# board.net
KiCad netlist of a schematic drawn in EAGLE
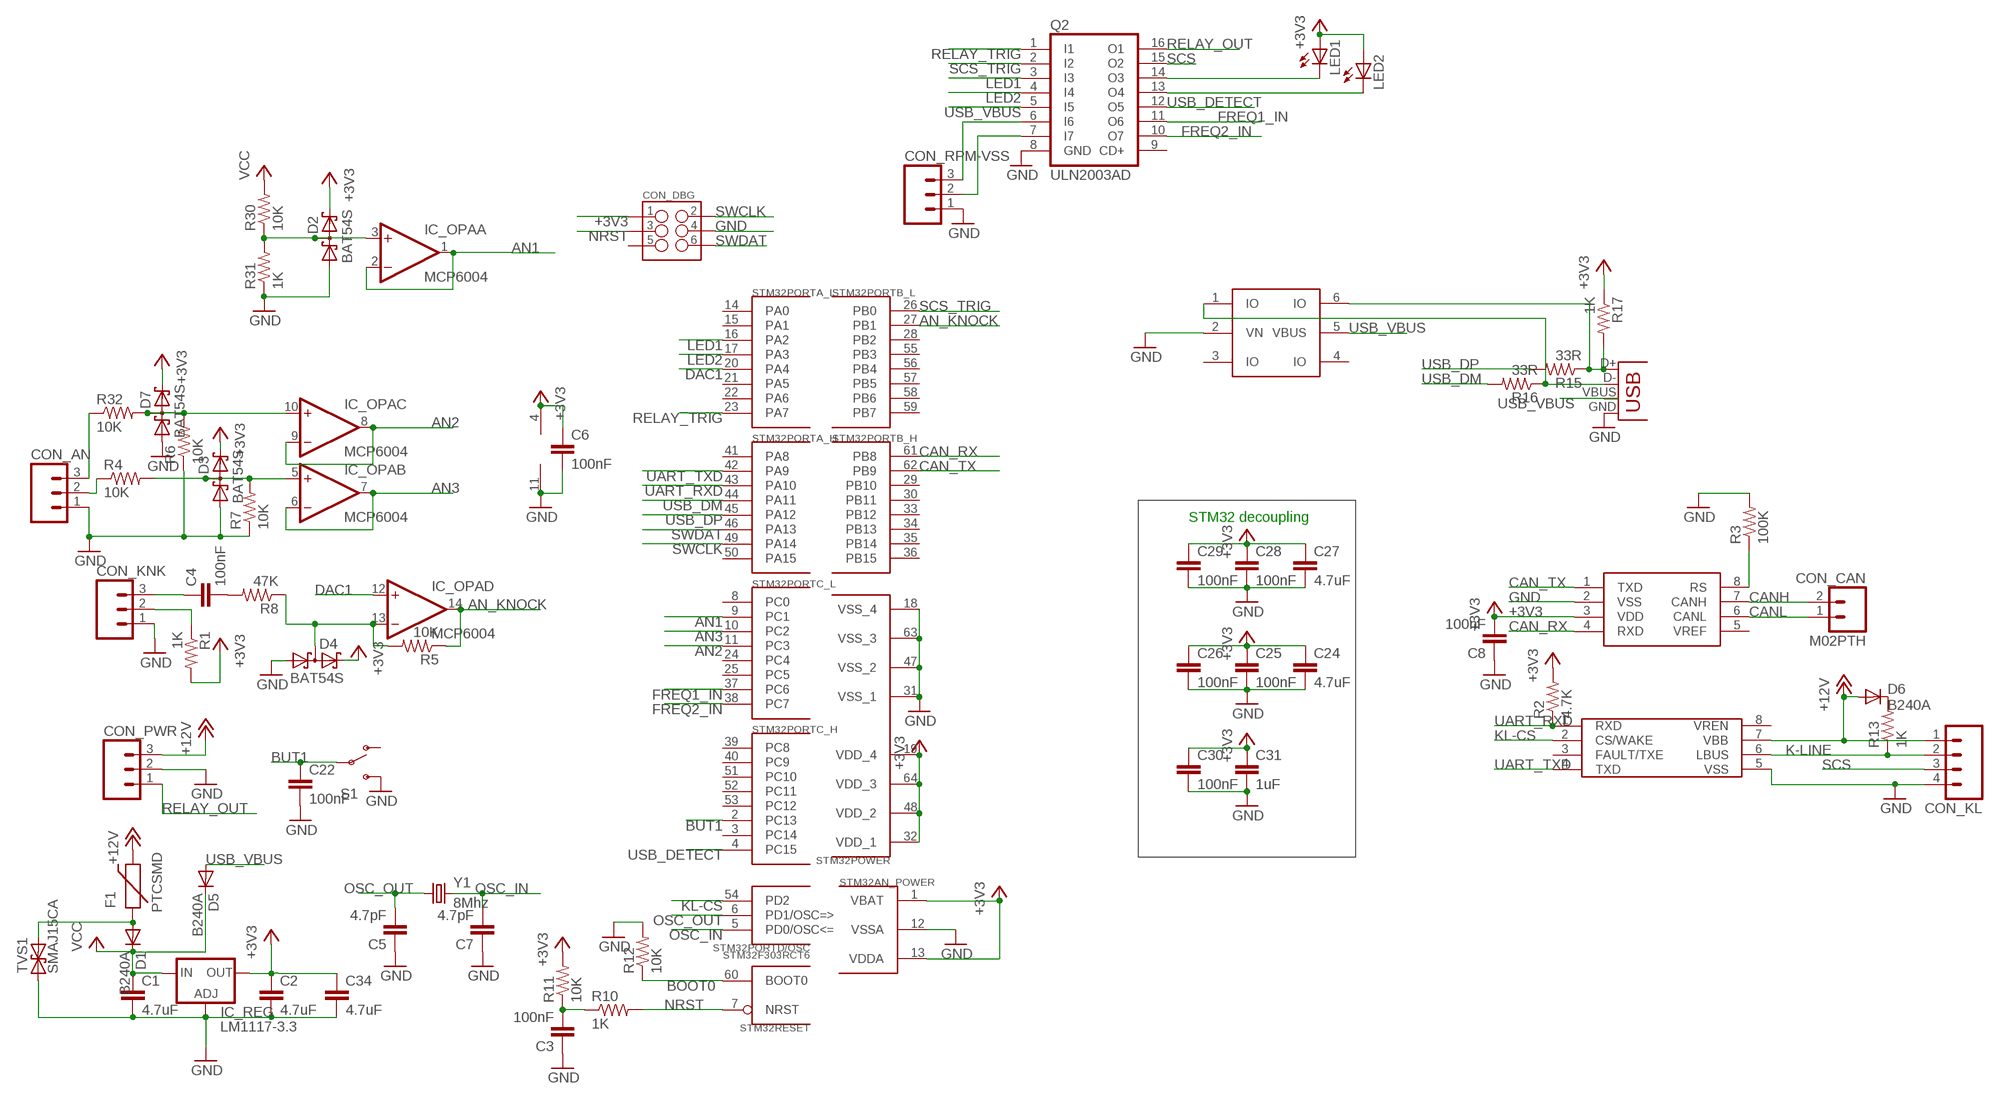
[diagram p0: schematic, sheet 1]

(export (version "E")
  (design (tool "Eeschema 10.0.6"))
  (components
    (comp (ref "C1")
      (value "4.7uF")
      (footprint "eagle-import:0603-CAP")
      (libsource (lib "eagle-import") (part "SparkFun-Passives_CAP0603-CAP"))
    )
    (comp (ref "C2")
      (value "4.7uF")
      (footprint "eagle-import:0603-CAP")
      (libsource (lib "eagle-import") (part "SparkFun-Passives_CAP0603-CAP"))
    )
    (comp (ref "C3")
      (value "100nF")
      (footprint "eagle-import:0603-CAP")
      (libsource (lib "eagle-import") (part "CAP0603-CAP"))
    )
    (comp (ref "C4")
      (value "100nF")
      (footprint "eagle-import:0603-CAP")
      (libsource (lib "eagle-import") (part "CAP0603-CAP"))
    )
    (comp (ref "C5")
      (value "4.7pF")
      (footprint "eagle-import:0603-CAP")
      (libsource (lib "eagle-import") (part "CAP0603-CAP"))
    )
    (comp (ref "C6")
      (value "100nF")
      (footprint "eagle-import:0603-CAP")
      (libsource (lib "eagle-import") (part "CAP0603-CAP"))
    )
    (comp (ref "C7")
      (value "4.7pF")
      (footprint "eagle-import:0603-CAP")
      (libsource (lib "eagle-import") (part "CAP0603-CAP"))
    )
    (comp (ref "C8")
      (value "100nF")
      (footprint "eagle-import:0603-CAP")
      (libsource (lib "eagle-import") (part "CAP0603-CAP"))
    )
    (comp (ref "C22")
      (value "100nF")
      (footprint "eagle-import:0603-CAP")
      (libsource (lib "eagle-import") (part "CAP0603-CAP"))
    )
    (comp (ref "C24")
      (value "4.7uF")
      (footprint "eagle-import:0603-CAP")
      (libsource (lib "eagle-import") (part "SparkFun-Passives_CAP0603-CAP"))
    )
    (comp (ref "C25")
      (value "100nF")
      (footprint "eagle-import:0603-CAP")
      (libsource (lib "eagle-import") (part "CAP0603-CAP"))
    )
    (comp (ref "C26")
      (value "100nF")
      (footprint "eagle-import:0603-CAP")
      (libsource (lib "eagle-import") (part "CAP0603-CAP"))
    )
    (comp (ref "C27")
      (value "4.7uF")
      (footprint "eagle-import:0603-CAP")
      (libsource (lib "eagle-import") (part "SparkFun-Passives_CAP0603-CAP"))
    )
    (comp (ref "C28")
      (value "100nF")
      (footprint "eagle-import:0603-CAP")
      (libsource (lib "eagle-import") (part "CAP0603-CAP"))
    )
    (comp (ref "C29")
      (value "100nF")
      (footprint "eagle-import:0603-CAP")
      (libsource (lib "eagle-import") (part "CAP0603-CAP"))
    )
    (comp (ref "C30")
      (value "100nF")
      (footprint "eagle-import:0603-CAP")
      (libsource (lib "eagle-import") (part "CAP0603-CAP"))
    )
    (comp (ref "C31")
      (value "1uF")
      (footprint "eagle-import:0603-CAP")
      (libsource (lib "eagle-import") (part "CAP0603-CAP"))
    )
    (comp (ref "C34")
      (value "4.7uF")
      (footprint "eagle-import:0603-CAP")
      (libsource (lib "eagle-import") (part "SparkFun-Passives_CAP0603-CAP"))
    )
    (comp (ref "CON_AN")
      (value "M03PTH")
      (footprint "eagle-import:1X03")
      (libsource (lib "eagle-import") (part "M03PTH"))
    )
    (comp (ref "CON_CAN")
      (value "M02PTH")
      (footprint "eagle-import:1X02")
      (libsource (lib "eagle-import") (part "M02PTH"))
    )
    (comp (ref "CON_DBG")
      (value "M03X22X3_SILK_SM")
      (footprint "eagle-import:2X3")
      (libsource (lib "eagle-import") (part "M03X22X3_SILK_SM"))
    )
    (comp (ref "CON_KL")
      (value "M04PTH")
      (footprint "eagle-import:1X04")
      (libsource (lib "eagle-import") (part "M04PTH"))
    )
    (comp (ref "CON_KNK")
      (value "M03PTH")
      (footprint "eagle-import:1X03")
      (libsource (lib "eagle-import") (part "M03PTH"))
    )
    (comp (ref "CON_PWR")
      (value "M03PTH")
      (footprint "eagle-import:1X03")
      (libsource (lib "eagle-import") (part "M03PTH"))
    )
    (comp (ref "CON_RPM-VSS")
      (value "M03PTH")
      (footprint "eagle-import:1X03")
      (libsource (lib "eagle-import") (part "M03PTH"))
    )
    (comp (ref "D1")
      (value "B240A")
      (footprint "eagle-import:SMA-DIODE")
      (libsource (lib "eagle-import") (part "DIODESMA"))
    )
    (comp (ref "D2")
      (value "BAT54S")
      (footprint "eagle-import:SOT23")
      (libsource (lib "eagle-import") (part "BAT54S"))
    )
    (comp (ref "D3")
      (value "BAT54S")
      (footprint "eagle-import:SOT23")
      (libsource (lib "eagle-import") (part "BAT54S"))
    )
    (comp (ref "D4")
      (value "BAT54S")
      (footprint "eagle-import:SOT23")
      (libsource (lib "eagle-import") (part "BAT54S"))
    )
    (comp (ref "D5")
      (value "B240A")
      (footprint "eagle-import:SMA-DIODE")
      (libsource (lib "eagle-import") (part "DIODESMA"))
    )
    (comp (ref "D6")
      (value "B240A")
      (footprint "eagle-import:SMA-DIODE")
      (libsource (lib "eagle-import") (part "DIODESMA"))
    )
    (comp (ref "D7")
      (value "BAT54S")
      (footprint "eagle-import:SOT23")
      (libsource (lib "eagle-import") (part "BAT54S"))
    )
    (comp (ref "F1")
      (value "PTCSMD")
      (footprint "eagle-import:PTC-1206")
      (libsource (lib "eagle-import") (part "PTCSMD"))
    )
    (comp (ref "IC_CAN")
      (value "MAX3051")
      (footprint "eagle-import:SO08")
      (libsource (lib "eagle-import") (part "MCP2551"))
    )
    (comp (ref "IC_KLINE")
      (value "MCP2004")
      (footprint "eagle-import:SO08")
      (libsource (lib "eagle-import") (part "MCP2004"))
    )
    (comp (ref "IC_OPA")
      (value "MCP6004")
      (footprint "eagle-import:TSSOP14")
      (libsource (lib "eagle-import") (part "LMV324?MZ"))
    )
    (comp (ref "IC_REG")
      (value "LM1117-3.3")
      (footprint "eagle-import:DPACK")
      (libsource (lib "eagle-import") (part "LD117A?DT33TR"))
    )
    (comp (ref "JP1")
      (value "USBSMD")
      (footprint "eagle-import:USB-MINIB")
      (libsource (lib "eagle-import") (part "USBSMD"))
    )
    (comp (ref "LED1")
      (value "LED3MM")
      (footprint "eagle-import:LED3MM")
      (libsource (lib "eagle-import") (part "LED3MM"))
    )
    (comp (ref "LED2")
      (value "LED3MM")
      (footprint "eagle-import:LED3MM")
      (libsource (lib "eagle-import") (part "LED3MM"))
    )
    (comp (ref "Q2")
      (value "ULN2003AD")
      (footprint "eagle-import:SO16")
      (libsource (lib "eagle-import") (part "ULN2003AD"))
    )
    (comp (ref "R1")
      (value "1K")
      (footprint "eagle-import:0603-RES")
      (libsource (lib "eagle-import") (part "RESISTOR0603-RES"))
    )
    (comp (ref "R2")
      (value "4.7K")
      (footprint "eagle-import:0603-RES")
      (libsource (lib "eagle-import") (part "RESISTOR0603-RES"))
    )
    (comp (ref "R3")
      (value "100K")
      (footprint "eagle-import:0603-RES")
      (libsource (lib "eagle-import") (part "RESISTOR0603-RES"))
    )
    (comp (ref "R4")
      (value "10K")
      (footprint "eagle-import:0603-RES")
      (libsource (lib "eagle-import") (part "RESISTOR0603-RES"))
    )
    (comp (ref "R5")
      (value "10K")
      (footprint "eagle-import:0603-RES")
      (libsource (lib "eagle-import") (part "RESISTOR0603-RES"))
    )
    (comp (ref "R6")
      (value "10K")
      (footprint "eagle-import:0603-RES")
      (libsource (lib "eagle-import") (part "RESISTOR0603-RES"))
    )
    (comp (ref "R7")
      (value "10K")
      (footprint "eagle-import:0603-RES")
      (libsource (lib "eagle-import") (part "RESISTOR0603-RES"))
    )
    (comp (ref "R8")
      (value "47K")
      (footprint "eagle-import:0603-RES")
      (libsource (lib "eagle-import") (part "RESISTOR0603-RES"))
    )
    (comp (ref "R10")
      (value "1K")
      (footprint "eagle-import:0603-RES")
      (libsource (lib "eagle-import") (part "RESISTOR0603-RES"))
    )
    (comp (ref "R11")
      (value "10K")
      (footprint "eagle-import:0603-RES")
      (libsource (lib "eagle-import") (part "RESISTOR0603-RES"))
    )
    (comp (ref "R12")
      (value "10K")
      (footprint "eagle-import:0603-RES")
      (libsource (lib "eagle-import") (part "RESISTOR0603-RES"))
    )
    (comp (ref "R13")
      (value "1K")
      (footprint "eagle-import:0603-RES")
      (libsource (lib "eagle-import") (part "RESISTOR0603-RES"))
    )
    (comp (ref "R15")
      (value "33R")
      (footprint "eagle-import:0603-RES")
      (libsource (lib "eagle-import") (part "RESISTOR0603-RES"))
    )
    (comp (ref "R16")
      (value "33R")
      (footprint "eagle-import:0603-RES")
      (libsource (lib "eagle-import") (part "RESISTOR0603-RES"))
    )
    (comp (ref "R17")
      (value "1K")
      (footprint "eagle-import:0603-RES")
      (libsource (lib "eagle-import") (part "RESISTOR0603-RES"))
    )
    (comp (ref "R30")
      (value "10K")
      (footprint "eagle-import:0603-RES")
      (libsource (lib "eagle-import") (part "RESISTOR0603-RES"))
    )
    (comp (ref "R31")
      (value "1K")
      (footprint "eagle-import:0603-RES")
      (libsource (lib "eagle-import") (part "RESISTOR0603-RES"))
    )
    (comp (ref "R32")
      (value "10K")
      (footprint "eagle-import:0603-RES")
      (libsource (lib "eagle-import") (part "RESISTOR0603-RES"))
    )
    (comp (ref "S1")
      (value "SWITCH-SPDTPTH")
      (footprint "eagle-import:SWITCH-SPDT")
      (libsource (lib "eagle-import") (part "SWITCH-SPDTPTH"))
    )
    (comp (ref "STM32")
      (value "STM32F303RCT6")
      (footprint "eagle-import:TQFP64")
      (libsource (lib "eagle-import") (part "STM32F10XRXT6"))
    )
    (comp (ref "TVS1")
      (value "SMAJ15CA")
      (footprint "eagle-import:SMA-DIODE")
      (libsource (lib "eagle-import") (part "TVS"))
    )
    (comp (ref "TVS2")
      (value "NUP4201MR6")
      (footprint "eagle-import:SOT23-6")
      (libsource (lib "eagle-import") (part "NUP4201MR6"))
    )
    (comp (ref "Y1")
      (value "8Mhz")
      (footprint "eagle-import:HC49US")
      (libsource (lib "eagle-import") (part "CRYSTALHC49US"))
    )
  )
  (nets
    (net (code "1") (name "+3V3") (class "Default")
      (node (ref "C2") (pin "1") (pinfunction "1_1") (pintype "passive"))
      (node (ref "C24") (pin "1") (pinfunction "1_1") (pintype "passive"))
      (node (ref "C25") (pin "1") (pinfunction "1_1") (pintype "passive"))
      (node (ref "C26") (pin "1") (pinfunction "1_1") (pintype "passive"))
      (node (ref "C27") (pin "1") (pinfunction "1_1") (pintype "passive"))
      (node (ref "C28") (pin "1") (pinfunction "1_1") (pintype "passive"))
      (node (ref "C29") (pin "1") (pinfunction "1_1") (pintype "passive"))
      (node (ref "C30") (pin "1") (pinfunction "1_1") (pintype "passive"))
      (node (ref "C31") (pin "1") (pinfunction "1_1") (pintype "passive"))
      (node (ref "C34") (pin "1") (pinfunction "1_1") (pintype "passive"))
      (node (ref "C6") (pin "1") (pinfunction "1_1") (pintype "passive"))
      (node (ref "C8") (pin "2") (pinfunction "2_2") (pintype "passive"))
      (node (ref "CON_DBG") (pin "1") (pinfunction "1_1") (pintype "bidirectional"))
      (node (ref "D2") (pin "2") (pinfunction "C2_2") (pintype "passive"))
      (node (ref "D3") (pin "2") (pinfunction "C2_2") (pintype "passive"))
      (node (ref "D4") (pin "2") (pinfunction "C2_2") (pintype "passive"))
      (node (ref "D7") (pin "2") (pinfunction "C2_2") (pintype "passive"))
      (node (ref "IC_CAN") (pin "3") (pinfunction "VDD_3") (pintype "bidirectional"))
      (node (ref "IC_OPA") (pin "4") (pinfunction "V+_4") (pintype "power_in"))
      (node (ref "IC_REG") (pin "4") (pinfunction "OUT_4") (pintype "passive"))
      (node (ref "LED1") (pin "A") (pinfunction "A_A") (pintype "passive"))
      (node (ref "LED2") (pin "A") (pinfunction "A_A") (pintype "passive"))
      (node (ref "R1") (pin "2") (pinfunction "2_2") (pintype "passive"))
      (node (ref "R11") (pin "2") (pinfunction "2_2") (pintype "passive"))
      (node (ref "R17") (pin "1") (pinfunction "1_1") (pintype "passive"))
      (node (ref "R2") (pin "2") (pinfunction "2_2") (pintype "passive"))
      (node (ref "STM32") (pin "1") (pinfunction "VBAT_1") (pintype "power_in"))
      (node (ref "STM32") (pin "13") (pinfunction "VDDA_13") (pintype "power_in"))
      (node (ref "STM32") (pin "19") (pinfunction "VDD_4_19") (pintype "power_in"))
      (node (ref "STM32") (pin "32") (pinfunction "VDD_1_32") (pintype "power_in"))
      (node (ref "STM32") (pin "48") (pinfunction "VDD_2_48") (pintype "power_in"))
      (node (ref "STM32") (pin "64") (pinfunction "VDD_3_64") (pintype "power_in"))
    )
    (net (code "2") (name "+12V") (class "Default")
      (node (ref "CON_KL") (pin "1") (pinfunction "1_1") (pintype "passive"))
      (node (ref "CON_PWR") (pin "3") (pinfunction "3_3") (pintype "passive"))
      (node (ref "D6") (pin "A") (pinfunction "A_A") (pintype "passive"))
      (node (ref "F1") (pin "2") (pinfunction "2_2") (pintype "bidirectional"))
      (node (ref "IC_KLINE") (pin "7") (pinfunction "VBB_7") (pintype "bidirectional"))
    )
    (net (code "3") (name "/AN1") (class "Default")
      (node (ref "IC_OPA") (pin "1") (pinfunction "OUT_1") (pintype "output"))
      (node (ref "IC_OPA") (pin "2") (pinfunction "-IN_2") (pintype "input"))
      (node (ref "STM32") (pin "9") (pinfunction "PC1_9") (pintype "bidirectional"))
    )
    (net (code "4") (name "/AN2") (class "Default")
      (node (ref "IC_OPA") (pin "8") (pinfunction "OUT_8") (pintype "output"))
      (node (ref "IC_OPA") (pin "9") (pinfunction "-IN_9") (pintype "input"))
      (node (ref "STM32") (pin "11") (pinfunction "PC3_11") (pintype "bidirectional"))
    )
    (net (code "5") (name "/AN3") (class "Default")
      (node (ref "IC_OPA") (pin "6") (pinfunction "-IN_6") (pintype "input"))
      (node (ref "IC_OPA") (pin "7") (pinfunction "OUT_7") (pintype "output"))
      (node (ref "STM32") (pin "10") (pinfunction "PC2_10") (pintype "bidirectional"))
    )
    (net (code "6") (name "/AN_KNOCK") (class "Default")
      (node (ref "IC_OPA") (pin "14") (pinfunction "OUT_14") (pintype "output"))
      (node (ref "R5") (pin "1") (pinfunction "1_1") (pintype "passive"))
      (node (ref "STM32") (pin "27") (pinfunction "PB1_27") (pintype "bidirectional"))
    )
    (net (code "7") (name "/BOOT0") (class "Default")
      (node (ref "R12") (pin "1") (pinfunction "1_1") (pintype "passive"))
      (node (ref "STM32") (pin "60") (pinfunction "BOOT0_60") (pintype "input"))
    )
    (net (code "8") (name "/BUT1") (class "Default")
      (node (ref "C22") (pin "1") (pinfunction "1_1") (pintype "passive"))
      (node (ref "S1") (pin "2") (pinfunction "P_2") (pintype "passive"))
      (node (ref "STM32") (pin "2") (pinfunction "PC13_2") (pintype "bidirectional"))
    )
    (net (code "9") (name "/CANH") (class "Default")
      (node (ref "CON_CAN") (pin "2") (pinfunction "2_2") (pintype "passive"))
      (node (ref "IC_CAN") (pin "7") (pinfunction "CANH_7") (pintype "bidirectional"))
    )
    (net (code "10") (name "/CANL") (class "Default")
      (node (ref "CON_CAN") (pin "1") (pinfunction "1_1") (pintype "passive"))
      (node (ref "IC_CAN") (pin "6") (pinfunction "CANL_6") (pintype "bidirectional"))
    )
    (net (code "11") (name "/CAN_RX") (class "Default")
      (node (ref "IC_CAN") (pin "4") (pinfunction "RXD_4") (pintype "bidirectional"))
      (node (ref "STM32") (pin "61") (pinfunction "PB8_61") (pintype "bidirectional"))
    )
    (net (code "12") (name "/CAN_TX") (class "Default")
      (node (ref "IC_CAN") (pin "1") (pinfunction "TXD_1") (pintype "bidirectional"))
      (node (ref "STM32") (pin "62") (pinfunction "PB9_62") (pintype "bidirectional"))
    )
    (net (code "13") (name "/DAC1") (class "Default")
      (node (ref "IC_OPA") (pin "12") (pinfunction "+IN_12") (pintype "input"))
      (node (ref "STM32") (pin "20") (pinfunction "PA4_20") (pintype "bidirectional"))
    )
    (net (code "14") (name "/FREQ1_IN") (class "Default")
      (node (ref "Q2") (pin "11") (pinfunction "O6_11") (pintype "open_collector"))
      (node (ref "STM32") (pin "37") (pinfunction "PC6_37") (pintype "bidirectional"))
    )
    (net (code "15") (name "/FREQ2_IN") (class "Default")
      (node (ref "Q2") (pin "10") (pinfunction "O7_10") (pintype "open_collector"))
      (node (ref "STM32") (pin "38") (pinfunction "PC7_38") (pintype "bidirectional"))
    )
    (net (code "16") (name "/K-LINE") (class "Default")
      (node (ref "CON_KL") (pin "2") (pinfunction "2_2") (pintype "passive"))
      (node (ref "IC_KLINE") (pin "6") (pinfunction "LBUS_6") (pintype "bidirectional"))
      (node (ref "R13") (pin "1") (pinfunction "1_1") (pintype "passive"))
    )
    (net (code "17") (name "/KL-CS") (class "Default")
      (node (ref "IC_KLINE") (pin "2") (pinfunction "CS/WAKE_2") (pintype "bidirectional"))
      (node (ref "STM32") (pin "54") (pinfunction "PD2_54") (pintype "bidirectional"))
    )
    (net (code "18") (name "/LED1") (class "Default")
      (node (ref "Q2") (pin "3") (pinfunction "I3_3") (pintype "input"))
      (node (ref "STM32") (pin "16") (pinfunction "PA2_16") (pintype "bidirectional"))
    )
    (net (code "19") (name "/LED2") (class "Default")
      (node (ref "Q2") (pin "4") (pinfunction "I4_4") (pintype "input"))
      (node (ref "STM32") (pin "17") (pinfunction "PA3_17") (pintype "bidirectional"))
    )
    (net (code "20") (name "/NRST") (class "Default")
      (node (ref "CON_DBG") (pin "3") (pinfunction "3_3") (pintype "bidirectional"))
      (node (ref "R10") (pin "2") (pinfunction "2_2") (pintype "passive"))
      (node (ref "STM32") (pin "7") (pinfunction "NRST_7") (pintype "input"))
    )
    (net (code "21") (name "/OSC_IN") (class "Default")
      (node (ref "C7") (pin "2") (pinfunction "2_2") (pintype "passive"))
      (node (ref "STM32") (pin "5") (pinfunction "PD0/OSC<=_5") (pintype "bidirectional"))
      (node (ref "Y1") (pin "2") (pinfunction "2_2") (pintype "passive"))
    )
    (net (code "22") (name "/OSC_OUT") (class "Default")
      (node (ref "C5") (pin "2") (pinfunction "2_2") (pintype "passive"))
      (node (ref "STM32") (pin "6") (pinfunction "PD1/OSC=>_6") (pintype "bidirectional"))
      (node (ref "Y1") (pin "1") (pinfunction "1_1") (pintype "passive"))
    )
    (net (code "23") (name "/RELAY_OUT") (class "Default")
      (node (ref "CON_PWR") (pin "1") (pinfunction "1_1") (pintype "passive"))
      (node (ref "Q2") (pin "16") (pinfunction "O1_16") (pintype "open_collector"))
    )
    (net (code "24") (name "/RELAY_TRIG") (class "Default")
      (node (ref "Q2") (pin "1") (pinfunction "I1_1") (pintype "input"))
      (node (ref "STM32") (pin "23") (pinfunction "PA7_23") (pintype "bidirectional"))
    )
    (net (code "25") (name "/SCS") (class "Default")
      (node (ref "CON_KL") (pin "3") (pinfunction "3_3") (pintype "passive"))
      (node (ref "Q2") (pin "15") (pinfunction "O2_15") (pintype "open_collector"))
    )
    (net (code "26") (name "/SCS_TRIG") (class "Default")
      (node (ref "Q2") (pin "2") (pinfunction "I2_2") (pintype "input"))
      (node (ref "STM32") (pin "26") (pinfunction "PB0_26") (pintype "bidirectional"))
    )
    (net (code "27") (name "/SWCLK") (class "Default")
      (node (ref "CON_DBG") (pin "2") (pinfunction "2_2") (pintype "bidirectional"))
      (node (ref "STM32") (pin "49") (pinfunction "PA14_49") (pintype "bidirectional"))
    )
    (net (code "28") (name "/SWDAT") (class "Default")
      (node (ref "CON_DBG") (pin "6") (pinfunction "6_6") (pintype "bidirectional"))
      (node (ref "STM32") (pin "46") (pinfunction "PA13_46") (pintype "bidirectional"))
    )
    (net (code "29") (name "/UART_RXD") (class "Default")
      (node (ref "IC_KLINE") (pin "1") (pinfunction "RXD_1") (pintype "bidirectional"))
      (node (ref "R2") (pin "1") (pinfunction "1_1") (pintype "passive"))
      (node (ref "STM32") (pin "43") (pinfunction "PA10_43") (pintype "bidirectional"))
    )
    (net (code "30") (name "/UART_TXD") (class "Default")
      (node (ref "IC_KLINE") (pin "4") (pinfunction "TXD_4") (pintype "bidirectional"))
      (node (ref "STM32") (pin "42") (pinfunction "PA9_42") (pintype "bidirectional"))
    )
    (net (code "31") (name "/USB_DETECT") (class "Default")
      (node (ref "Q2") (pin "12") (pinfunction "O5_12") (pintype "open_collector"))
      (node (ref "STM32") (pin "4") (pinfunction "PC15_4") (pintype "bidirectional"))
    )
    (net (code "32") (name "/USB_DM") (class "Default")
      (node (ref "R16") (pin "2") (pinfunction "2_2") (pintype "passive"))
      (node (ref "STM32") (pin "44") (pinfunction "PA11_44") (pintype "bidirectional"))
    )
    (net (code "33") (name "/USB_DP") (class "Default")
      (node (ref "R15") (pin "2") (pinfunction "2_2") (pintype "passive"))
      (node (ref "STM32") (pin "45") (pinfunction "PA12_45") (pintype "bidirectional"))
    )
    (net (code "34") (name "/USB_VBUS") (class "Default")
      (node (ref "D5") (pin "A") (pinfunction "A_A") (pintype "passive"))
      (node (ref "JP1") (pin "VBUS") (pinfunction "VBUS_VBUS") (pintype "bidirectional"))
      (node (ref "Q2") (pin "5") (pinfunction "I5_5") (pintype "input"))
      (node (ref "TVS2") (pin "5") (pinfunction "VBUS_5") (pintype "power_in"))
    )
    (net (code "35") (name "GND") (class "Default")
      (node (ref "C1") (pin "2") (pinfunction "2_2") (pintype "passive"))
      (node (ref "C2") (pin "2") (pinfunction "2_2") (pintype "passive"))
      (node (ref "C22") (pin "2") (pinfunction "2_2") (pintype "passive"))
      (node (ref "C24") (pin "2") (pinfunction "2_2") (pintype "passive"))
      (node (ref "C25") (pin "2") (pinfunction "2_2") (pintype "passive"))
      (node (ref "C26") (pin "2") (pinfunction "2_2") (pintype "passive"))
      (node (ref "C27") (pin "2") (pinfunction "2_2") (pintype "passive"))
      (node (ref "C28") (pin "2") (pinfunction "2_2") (pintype "passive"))
      (node (ref "C29") (pin "2") (pinfunction "2_2") (pintype "passive"))
      (node (ref "C3") (pin "1") (pinfunction "1_1") (pintype "passive"))
      (node (ref "C30") (pin "2") (pinfunction "2_2") (pintype "passive"))
      (node (ref "C31") (pin "2") (pinfunction "2_2") (pintype "passive"))
      (node (ref "C34") (pin "2") (pinfunction "2_2") (pintype "passive"))
      (node (ref "C5") (pin "1") (pinfunction "1_1") (pintype "passive"))
      (node (ref "C6") (pin "2") (pinfunction "2_2") (pintype "passive"))
      (node (ref "C7") (pin "1") (pinfunction "1_1") (pintype "passive"))
      (node (ref "C8") (pin "1") (pinfunction "1_1") (pintype "passive"))
      (node (ref "CON_AN") (pin "1") (pinfunction "1_1") (pintype "passive"))
      (node (ref "CON_DBG") (pin "4") (pinfunction "4_4") (pintype "bidirectional"))
      (node (ref "CON_KL") (pin "4") (pinfunction "4_4") (pintype "passive"))
      (node (ref "CON_KNK") (pin "1") (pinfunction "1_1") (pintype "passive"))
      (node (ref "CON_PWR") (pin "2") (pinfunction "2_2") (pintype "passive"))
      (node (ref "CON_RPM-VSS") (pin "1") (pinfunction "1_1") (pintype "passive"))
      (node (ref "D2") (pin "1") (pinfunction "A1_1") (pintype "passive"))
      (node (ref "D3") (pin "1") (pinfunction "A1_1") (pintype "passive"))
      (node (ref "D4") (pin "1") (pinfunction "A1_1") (pintype "passive"))
      (node (ref "D7") (pin "1") (pinfunction "A1_1") (pintype "passive"))
      (node (ref "IC_CAN") (pin "2") (pinfunction "VSS_2") (pintype "bidirectional"))
      (node (ref "IC_KLINE") (pin "5") (pinfunction "VSS_5") (pintype "bidirectional"))
      (node (ref "IC_OPA") (pin "11") (pinfunction "V-_11") (pintype "power_in"))
      (node (ref "IC_REG") (pin "1") (pinfunction "ADJ_1") (pintype "input"))
      (node (ref "JP1") (pin "GND") (pinfunction "GND_GND") (pintype "bidirectional"))
      (node (ref "Q2") (pin "8") (pinfunction "GND_8") (pintype "power_in"))
      (node (ref "R12") (pin "2") (pinfunction "2_2") (pintype "passive"))
      (node (ref "R3") (pin "2") (pinfunction "2_2") (pintype "passive"))
      (node (ref "R31") (pin "1") (pinfunction "1_1") (pintype "passive"))
      (node (ref "R6") (pin "1") (pinfunction "1_1") (pintype "passive"))
      (node (ref "R7") (pin "1") (pinfunction "1_1") (pintype "passive"))
      (node (ref "S1") (pin "3") (pinfunction "S_3") (pintype "passive"))
      (node (ref "STM32") (pin "12") (pinfunction "VSSA_12") (pintype "power_in"))
      (node (ref "STM32") (pin "18") (pinfunction "VSS_4_18") (pintype "power_in"))
      (node (ref "STM32") (pin "31") (pinfunction "VSS_1_31") (pintype "power_in"))
      (node (ref "STM32") (pin "47") (pinfunction "VSS_2_47") (pintype "power_in"))
      (node (ref "STM32") (pin "63") (pinfunction "VSS_3_63") (pintype "power_in"))
      (node (ref "TVS1") (pin "A") (pinfunction "1_A") (pintype "passive"))
      (node (ref "TVS2") (pin "2") (pinfunction "VN_2") (pintype "power_in"))
    )
    (net (code "36") (name "Net-(C3-Pad2)") (class "Default")
      (node (ref "C3") (pin "2") (pinfunction "2_2") (pintype "passive"))
      (node (ref "R10") (pin "1") (pinfunction "1_1") (pintype "passive"))
      (node (ref "R11") (pin "1") (pinfunction "1_1") (pintype "passive"))
    )
    (net (code "37") (name "Net-(C4-Pad1)") (class "Default")
      (node (ref "C4") (pin "1") (pinfunction "1_1") (pintype "passive"))
      (node (ref "CON_KNK") (pin "3") (pinfunction "3_3") (pintype "passive"))
    )
    (net (code "38") (name "Net-(C4-Pad2)") (class "Default")
      (node (ref "C4") (pin "2") (pinfunction "2_2") (pintype "passive"))
      (node (ref "R8") (pin "2") (pinfunction "2_2") (pintype "passive"))
    )
    (net (code "39") (name "Net-(CON_AN-Pad2)") (class "Default")
      (node (ref "CON_AN") (pin "2") (pinfunction "2_2") (pintype "passive"))
      (node (ref "R4") (pin "1") (pinfunction "1_1") (pintype "passive"))
    )
    (net (code "40") (name "Net-(CON_AN-Pad3)") (class "Default")
      (node (ref "CON_AN") (pin "3") (pinfunction "3_3") (pintype "passive"))
      (node (ref "R32") (pin "1") (pinfunction "1_1") (pintype "passive"))
    )
    (net (code "41") (name "Net-(CON_KNK-Pad2)") (class "Default")
      (node (ref "CON_KNK") (pin "2") (pinfunction "2_2") (pintype "passive"))
      (node (ref "R1") (pin "1") (pinfunction "1_1") (pintype "passive"))
    )
    (net (code "42") (name "Net-(D2-C1A2)") (class "Default")
      (node (ref "D2") (pin "3") (pinfunction "C1A2_3") (pintype "passive"))
      (node (ref "IC_OPA") (pin "3") (pinfunction "+IN_3") (pintype "input"))
      (node (ref "R30") (pin "1") (pinfunction "1_1") (pintype "passive"))
      (node (ref "R31") (pin "2") (pinfunction "2_2") (pintype "passive"))
    )
    (net (code "43") (name "Net-(D3-C1A2)") (class "Default")
      (node (ref "D3") (pin "3") (pinfunction "C1A2_3") (pintype "passive"))
      (node (ref "IC_OPA") (pin "5") (pinfunction "+IN_5") (pintype "input"))
      (node (ref "R4") (pin "2") (pinfunction "2_2") (pintype "passive"))
      (node (ref "R7") (pin "2") (pinfunction "2_2") (pintype "passive"))
    )
    (net (code "44") (name "Net-(D4-C1A2)") (class "Default")
      (node (ref "D4") (pin "3") (pinfunction "C1A2_3") (pintype "passive"))
      (node (ref "IC_OPA") (pin "13") (pinfunction "-IN_13") (pintype "input"))
      (node (ref "R5") (pin "2") (pinfunction "2_2") (pintype "passive"))
      (node (ref "R8") (pin "1") (pinfunction "1_1") (pintype "passive"))
    )
    (net (code "45") (name "Net-(D6-PadC)") (class "Default")
      (node (ref "D6") (pin "C") (pinfunction "C_C") (pintype "passive"))
      (node (ref "R13") (pin "2") (pinfunction "2_2") (pintype "passive"))
    )
    (net (code "46") (name "Net-(D7-C1A2)") (class "Default")
      (node (ref "D7") (pin "3") (pinfunction "C1A2_3") (pintype "passive"))
      (node (ref "IC_OPA") (pin "10") (pinfunction "+IN_10") (pintype "input"))
      (node (ref "R32") (pin "2") (pinfunction "2_2") (pintype "passive"))
      (node (ref "R6") (pin "2") (pinfunction "2_2") (pintype "passive"))
    )
    (net (code "47") (name "Net-(IC_CAN-RS)") (class "Default")
      (node (ref "IC_CAN") (pin "8") (pinfunction "RS_8") (pintype "bidirectional"))
      (node (ref "R3") (pin "1") (pinfunction "1_1") (pintype "passive"))
    )
    (net (code "48") (name "Net-(JP1-PadD+)") (class "Default")
      (node (ref "JP1") (pin "D+") (pinfunction "D+_D+") (pintype "bidirectional"))
      (node (ref "R15") (pin "1") (pinfunction "1_1") (pintype "passive"))
      (node (ref "R17") (pin "2") (pinfunction "2_2") (pintype "passive"))
      (node (ref "TVS2") (pin "6") (pinfunction "IO_6") (pintype "bidirectional"))
    )
    (net (code "49") (name "Net-(JP1-PadD-)") (class "Default")
      (node (ref "JP1") (pin "D-") (pinfunction "D-_D-") (pintype "bidirectional"))
      (node (ref "R16") (pin "1") (pinfunction "1_1") (pintype "passive"))
      (node (ref "TVS2") (pin "1") (pinfunction "IO_1") (pintype "bidirectional"))
    )
    (net (code "50") (name "Net-(LED1-C)") (class "Default")
      (node (ref "LED1") (pin "K") (pinfunction "C_K") (pintype "passive"))
      (node (ref "Q2") (pin "14") (pinfunction "O3_14") (pintype "open_collector"))
    )
    (net (code "51") (name "Net-(LED2-C)") (class "Default")
      (node (ref "LED2") (pin "K") (pinfunction "C_K") (pintype "passive"))
      (node (ref "Q2") (pin "13") (pinfunction "O4_13") (pintype "open_collector"))
    )
    (net (code "52") (name "Net-(Q2-I6)") (class "Default")
      (node (ref "CON_RPM-VSS") (pin "3") (pinfunction "3_3") (pintype "passive"))
      (node (ref "Q2") (pin "6") (pinfunction "I6_6") (pintype "input"))
    )
    (net (code "53") (name "Net-(Q2-I7)") (class "Default")
      (node (ref "CON_RPM-VSS") (pin "2") (pinfunction "2_2") (pintype "passive"))
      (node (ref "Q2") (pin "7") (pinfunction "I7_7") (pintype "input"))
    )
    (net (code "54") (name "Net-(TVS1-2)") (class "Default")
      (node (ref "D1") (pin "A") (pinfunction "A_A") (pintype "passive"))
      (node (ref "F1") (pin "1") (pinfunction "1_1") (pintype "bidirectional"))
      (node (ref "TVS1") (pin "C") (pinfunction "2_C") (pintype "passive"))
    )
    (net (code "55") (name "VCC") (class "Default")
      (node (ref "C1") (pin "1") (pinfunction "1_1") (pintype "passive"))
      (node (ref "D1") (pin "C") (pinfunction "C_C") (pintype "passive"))
      (node (ref "D5") (pin "C") (pinfunction "C_C") (pintype "passive"))
      (node (ref "IC_REG") (pin "3") (pinfunction "IN_3") (pintype "input"))
      (node (ref "R30") (pin "2") (pinfunction "2_2") (pintype "passive"))
    )
    (net (code "56") (name "unconnected-(CON_DBG-Pad5)") (class "Default")
      (node (ref "CON_DBG") (pin "5") (pinfunction "5_5") (pintype "bidirectional"))
    )
    (net (code "57") (name "unconnected-(IC_CAN-VREF-Pad5)") (class "Default")
      (node (ref "IC_CAN") (pin "5") (pinfunction "VREF_5") (pintype "bidirectional"))
    )
    (net (code "58") (name "unconnected-(IC_KLINE-FAULT{slash}TXE-Pad3)") (class "Default")
      (node (ref "IC_KLINE") (pin "3") (pinfunction "FAULT/TXE_3") (pintype "bidirectional"))
    )
    (net (code "59") (name "unconnected-(IC_KLINE-VREN-Pad8)") (class "Default")
      (node (ref "IC_KLINE") (pin "8") (pinfunction "VREN_8") (pintype "bidirectional"))
    )
    (net (code "60") (name "unconnected-(Q2-CD+-Pad9)") (class "Default")
      (node (ref "Q2") (pin "9") (pinfunction "CD+_9") (pintype "passive"))
    )
    (net (code "61") (name "unconnected-(S1-O-Pad1)") (class "Default")
      (node (ref "S1") (pin "1") (pinfunction "O_1") (pintype "passive"))
    )
    (net (code "62") (name "unconnected-(STM32B-PA8-Pad41)") (class "Default")
      (node (ref "STM32") (pin "41") (pinfunction "PA8_41") (pintype "bidirectional"))
    )
    (net (code "63") (name "unconnected-(STM32B-PA15-Pad50)") (class "Default")
      (node (ref "STM32") (pin "50") (pinfunction "PA15_50") (pintype "bidirectional"))
    )
    (net (code "64") (name "unconnected-(STM32C-PA0-Pad14)") (class "Default")
      (node (ref "STM32") (pin "14") (pinfunction "PA0_14") (pintype "bidirectional"))
    )
    (net (code "65") (name "unconnected-(STM32C-PA1-Pad15)") (class "Default")
      (node (ref "STM32") (pin "15") (pinfunction "PA1_15") (pintype "bidirectional"))
    )
    (net (code "66") (name "unconnected-(STM32C-PA5-Pad21)") (class "Default")
      (node (ref "STM32") (pin "21") (pinfunction "PA5_21") (pintype "bidirectional"))
    )
    (net (code "67") (name "unconnected-(STM32C-PA6-Pad22)") (class "Default")
      (node (ref "STM32") (pin "22") (pinfunction "PA6_22") (pintype "bidirectional"))
    )
    (net (code "68") (name "unconnected-(STM32D-PB10-Pad29)") (class "Default")
      (node (ref "STM32") (pin "29") (pinfunction "PB10_29") (pintype "bidirectional"))
    )
    (net (code "69") (name "unconnected-(STM32D-PB11-Pad30)") (class "Default")
      (node (ref "STM32") (pin "30") (pinfunction "PB11_30") (pintype "bidirectional"))
    )
    (net (code "70") (name "unconnected-(STM32D-PB12-Pad33)") (class "Default")
      (node (ref "STM32") (pin "33") (pinfunction "PB12_33") (pintype "bidirectional"))
    )
    (net (code "71") (name "unconnected-(STM32D-PB13-Pad34)") (class "Default")
      (node (ref "STM32") (pin "34") (pinfunction "PB13_34") (pintype "bidirectional"))
    )
    (net (code "72") (name "unconnected-(STM32D-PB14-Pad35)") (class "Default")
      (node (ref "STM32") (pin "35") (pinfunction "PB14_35") (pintype "bidirectional"))
    )
    (net (code "73") (name "unconnected-(STM32D-PB15-Pad36)") (class "Default")
      (node (ref "STM32") (pin "36") (pinfunction "PB15_36") (pintype "bidirectional"))
    )
    (net (code "74") (name "unconnected-(STM32E-PB2-Pad28)") (class "Default")
      (node (ref "STM32") (pin "28") (pinfunction "PB2_28") (pintype "bidirectional"))
    )
    (net (code "75") (name "unconnected-(STM32E-PB3-Pad55)") (class "Default")
      (node (ref "STM32") (pin "55") (pinfunction "PB3_55") (pintype "bidirectional"))
    )
    (net (code "76") (name "unconnected-(STM32E-PB4-Pad56)") (class "Default")
      (node (ref "STM32") (pin "56") (pinfunction "PB4_56") (pintype "bidirectional"))
    )
    (net (code "77") (name "unconnected-(STM32E-PB5-Pad57)") (class "Default")
      (node (ref "STM32") (pin "57") (pinfunction "PB5_57") (pintype "bidirectional"))
    )
    (net (code "78") (name "unconnected-(STM32E-PB6-Pad58)") (class "Default")
      (node (ref "STM32") (pin "58") (pinfunction "PB6_58") (pintype "bidirectional"))
    )
    (net (code "79") (name "unconnected-(STM32E-PB7-Pad59)") (class "Default")
      (node (ref "STM32") (pin "59") (pinfunction "PB7_59") (pintype "bidirectional"))
    )
    (net (code "80") (name "unconnected-(STM32F-PC8-Pad39)") (class "Default")
      (node (ref "STM32") (pin "39") (pinfunction "PC8_39") (pintype "bidirectional"))
    )
    (net (code "81") (name "unconnected-(STM32F-PC9-Pad40)") (class "Default")
      (node (ref "STM32") (pin "40") (pinfunction "PC9_40") (pintype "bidirectional"))
    )
    (net (code "82") (name "unconnected-(STM32F-PC10-Pad51)") (class "Default")
      (node (ref "STM32") (pin "51") (pinfunction "PC10_51") (pintype "bidirectional"))
    )
    (net (code "83") (name "unconnected-(STM32F-PC11-Pad52)") (class "Default")
      (node (ref "STM32") (pin "52") (pinfunction "PC11_52") (pintype "bidirectional"))
    )
    (net (code "84") (name "unconnected-(STM32F-PC12-Pad53)") (class "Default")
      (node (ref "STM32") (pin "53") (pinfunction "PC12_53") (pintype "bidirectional"))
    )
    (net (code "85") (name "unconnected-(STM32F-PC14-Pad3)") (class "Default")
      (node (ref "STM32") (pin "3") (pinfunction "PC14_3") (pintype "bidirectional"))
    )
    (net (code "86") (name "unconnected-(STM32G-PC0-Pad8)") (class "Default")
      (node (ref "STM32") (pin "8") (pinfunction "PC0_8") (pintype "bidirectional"))
    )
    (net (code "87") (name "unconnected-(STM32G-PC4-Pad24)") (class "Default")
      (node (ref "STM32") (pin "24") (pinfunction "PC4_24") (pintype "bidirectional"))
    )
    (net (code "88") (name "unconnected-(STM32G-PC5-Pad25)") (class "Default")
      (node (ref "STM32") (pin "25") (pinfunction "PC5_25") (pintype "bidirectional"))
    )
    (net (code "89") (name "unconnected-(TVS2-IO-Pad3)") (class "Default")
      (node (ref "TVS2") (pin "3") (pinfunction "IO_3") (pintype "bidirectional"))
    )
    (net (code "90") (name "unconnected-(TVS2-IO-Pad4)") (class "Default")
      (node (ref "TVS2") (pin "4") (pinfunction "IO_4") (pintype "bidirectional"))
    )
  )
)
